# 15_BOOT.net
KiCad netlist of a schematic drawn in Altium Designer
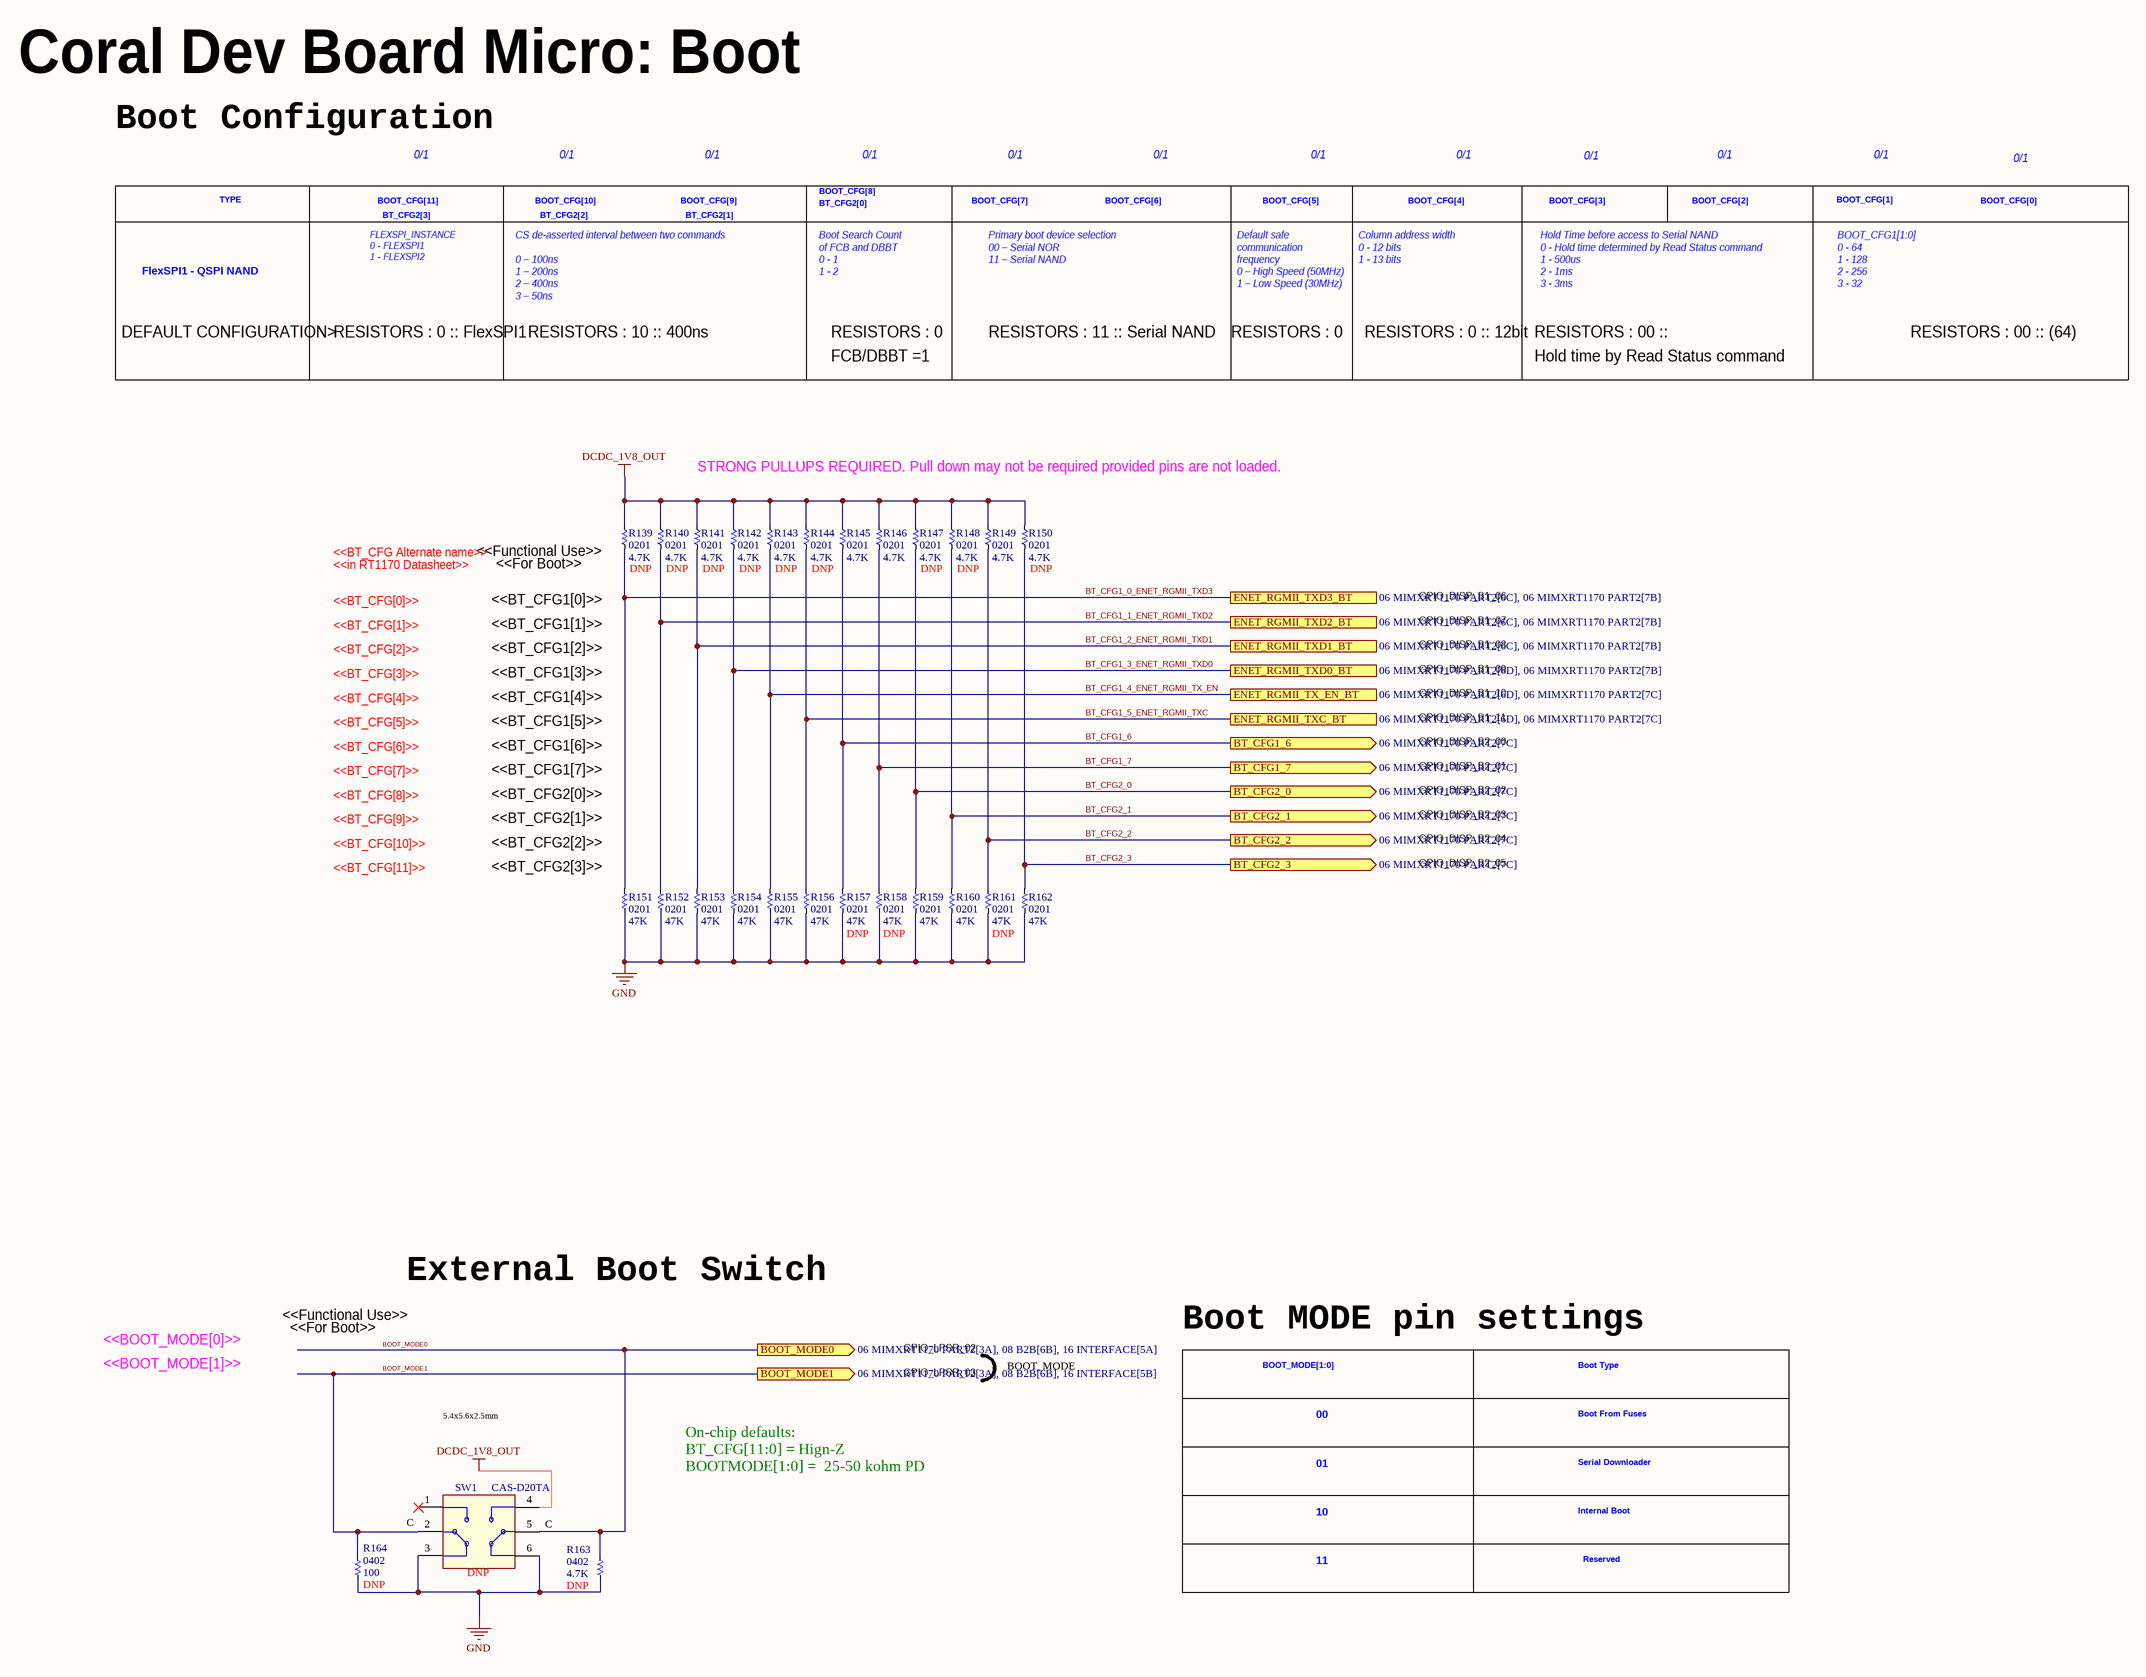
[diagram p0: 15 BOOT.SchDoc]

(export (version "E")
  (design (tool "Eeschema 10.0.6"))
  (components
    (comp (ref "R139")
      (value "4.7K")
      (footprint "R0201")
      (description "RES, 4.7K, 5%, 1/20W, 0201")
      (fields
        (field (name "MFG") "YAGEO")
        (field (name "PACKAGE") "0201")
        (field (name "POWER") "1/20W")
        (field (name "DNP") "DNP")
      )
      (libsource (lib "AltiumReleaseLibDB") (part "__Template_Resistor"))
    )
    (comp (ref "R140")
      (value "4.7K")
      (footprint "R0201")
      (description "RES, 4.7K, 5%, 1/20W, 0201")
      (fields
        (field (name "MFG") "YAGEO")
        (field (name "PACKAGE") "0201")
        (field (name "POWER") "1/20W")
        (field (name "DNP") "DNP")
      )
      (libsource (lib "AltiumReleaseLibDB") (part "__Template_Resistor"))
    )
    (comp (ref "R141")
      (value "4.7K")
      (footprint "R0201")
      (description "RES, 4.7K, 5%, 1/20W, 0201")
      (fields
        (field (name "MFG") "YAGEO")
        (field (name "PACKAGE") "0201")
        (field (name "POWER") "1/20W")
        (field (name "DNP") "DNP")
      )
      (libsource (lib "AltiumReleaseLibDB") (part "__Template_Resistor"))
    )
    (comp (ref "R142")
      (value "4.7K")
      (footprint "R0201")
      (description "RES, 4.7K, 5%, 1/20W, 0201")
      (fields
        (field (name "MFG") "YAGEO")
        (field (name "PACKAGE") "0201")
        (field (name "POWER") "1/20W")
        (field (name "DNP") "DNP")
      )
      (libsource (lib "AltiumReleaseLibDB") (part "__Template_Resistor"))
    )
    (comp (ref "R143")
      (value "4.7K")
      (footprint "R0201")
      (description "RES, 4.7K, 5%, 1/20W, 0201")
      (fields
        (field (name "MFG") "YAGEO")
        (field (name "PACKAGE") "0201")
        (field (name "POWER") "1/20W")
        (field (name "DNP") "DNP")
      )
      (libsource (lib "AltiumReleaseLibDB") (part "__Template_Resistor"))
    )
    (comp (ref "R144")
      (value "4.7K")
      (footprint "R0201")
      (description "RES, 4.7K, 5%, 1/20W, 0201")
      (fields
        (field (name "MFG") "YAGEO")
        (field (name "PACKAGE") "0201")
        (field (name "POWER") "1/20W")
        (field (name "DNP") "DNP")
      )
      (libsource (lib "AltiumReleaseLibDB") (part "__Template_Resistor"))
    )
    (comp (ref "R145")
      (value "4.7K")
      (footprint "R0201")
      (description "RES, 4.7K, 5%, 1/20W, 0201")
      (fields (field (name "MFG") "YAGEO") (field (name "PACKAGE") "0201") (field (name "POWER") "1/20W"))
      (libsource (lib "AltiumReleaseLibDB") (part "__Template_Resistor"))
    )
    (comp (ref "R146")
      (value "4.7K")
      (footprint "R0201")
      (description "RES, 4.7K, 5%, 1/20W, 0201")
      (fields (field (name "MFG") "YAGEO") (field (name "PACKAGE") "0201") (field (name "POWER") "1/20W"))
      (libsource (lib "AltiumReleaseLibDB") (part "__Template_Resistor"))
    )
    (comp (ref "R147")
      (value "4.7K")
      (footprint "R0201")
      (description "RES, 4.7K, 5%, 1/20W, 0201")
      (fields
        (field (name "MFG") "YAGEO")
        (field (name "PACKAGE") "0201")
        (field (name "POWER") "1/20W")
        (field (name "DNP") "DNP")
      )
      (libsource (lib "AltiumReleaseLibDB") (part "__Template_Resistor"))
    )
    (comp (ref "R148")
      (value "4.7K")
      (footprint "R0201")
      (description "RES, 4.7K, 5%, 1/20W, 0201")
      (fields
        (field (name "MFG") "YAGEO")
        (field (name "PACKAGE") "0201")
        (field (name "POWER") "1/20W")
        (field (name "DNP") "DNP")
      )
      (libsource (lib "AltiumReleaseLibDB") (part "__Template_Resistor"))
    )
    (comp (ref "R149")
      (value "4.7K")
      (footprint "R0201")
      (description "RES, 4.7K, 5%, 1/20W, 0201")
      (fields (field (name "MFG") "YAGEO") (field (name "PACKAGE") "0201") (field (name "POWER") "1/20W"))
      (libsource (lib "AltiumReleaseLibDB") (part "__Template_Resistor"))
    )
    (comp (ref "R150")
      (value "4.7K")
      (footprint "R0201")
      (description "RES, 4.7K, 5%, 1/20W, 0201")
      (fields
        (field (name "MFG") "YAGEO")
        (field (name "PACKAGE") "0201")
        (field (name "POWER") "1/20W")
        (field (name "DNP") "DNP")
      )
      (libsource (lib "AltiumReleaseLibDB") (part "__Template_Resistor"))
    )
    (comp (ref "R151")
      (value "47K")
      (footprint "R0201")
      (description "RES, 47K, 5%, 1/20W, 0201")
      (fields (field (name "MFG") "PANASONIC") (field (name "PACKAGE") "0201") (field (name "POWER") "1/20W"))
      (libsource (lib "AltiumReleaseLibDB") (part "__Template_Resistor"))
    )
    (comp (ref "R152")
      (value "47K")
      (footprint "R0201")
      (description "RES, 47K, 5%, 1/20W, 0201")
      (fields (field (name "MFG") "PANASONIC") (field (name "PACKAGE") "0201") (field (name "POWER") "1/20W"))
      (libsource (lib "AltiumReleaseLibDB") (part "__Template_Resistor"))
    )
    (comp (ref "R153")
      (value "47K")
      (footprint "R0201")
      (description "RES, 47K, 5%, 1/20W, 0201")
      (fields (field (name "MFG") "PANASONIC") (field (name "PACKAGE") "0201") (field (name "POWER") "1/20W"))
      (libsource (lib "AltiumReleaseLibDB") (part "__Template_Resistor"))
    )
    (comp (ref "R154")
      (value "47K")
      (footprint "R0201")
      (description "RES, 47K, 5%, 1/20W, 0201")
      (fields (field (name "MFG") "PANASONIC") (field (name "PACKAGE") "0201") (field (name "POWER") "1/20W"))
      (libsource (lib "AltiumReleaseLibDB") (part "__Template_Resistor"))
    )
    (comp (ref "R155")
      (value "47K")
      (footprint "R0201")
      (description "RES, 47K, 5%, 1/20W, 0201")
      (fields (field (name "MFG") "PANASONIC") (field (name "PACKAGE") "0201") (field (name "POWER") "1/20W"))
      (libsource (lib "AltiumReleaseLibDB") (part "__Template_Resistor"))
    )
    (comp (ref "R156")
      (value "47K")
      (footprint "R0201")
      (description "RES, 47K, 5%, 1/20W, 0201")
      (fields (field (name "MFG") "PANASONIC") (field (name "PACKAGE") "0201") (field (name "POWER") "1/20W"))
      (libsource (lib "AltiumReleaseLibDB") (part "__Template_Resistor"))
    )
    (comp (ref "R157")
      (value "47K")
      (footprint "R0201")
      (description "RES, 47K, 5%, 1/20W, 0201")
      (fields
        (field (name "MFG") "PANASONIC")
        (field (name "PACKAGE") "0201")
        (field (name "POWER") "1/20W")
        (field (name "DNP") "DNP")
      )
      (libsource (lib "AltiumReleaseLibDB") (part "__Template_Resistor"))
    )
    (comp (ref "R158")
      (value "47K")
      (footprint "R0201")
      (description "RES, 47K, 5%, 1/20W, 0201")
      (fields
        (field (name "MFG") "PANASONIC")
        (field (name "PACKAGE") "0201")
        (field (name "POWER") "1/20W")
        (field (name "DNP") "DNP")
      )
      (libsource (lib "AltiumReleaseLibDB") (part "__Template_Resistor"))
    )
    (comp (ref "R159")
      (value "47K")
      (footprint "R0201")
      (description "RES, 47K, 5%, 1/20W, 0201")
      (fields (field (name "MFG") "PANASONIC") (field (name "PACKAGE") "0201") (field (name "POWER") "1/20W"))
      (libsource (lib "AltiumReleaseLibDB") (part "__Template_Resistor"))
    )
    (comp (ref "R160")
      (value "47K")
      (footprint "R0201")
      (description "RES, 47K, 5%, 1/20W, 0201")
      (fields (field (name "MFG") "PANASONIC") (field (name "PACKAGE") "0201") (field (name "POWER") "1/20W"))
      (libsource (lib "AltiumReleaseLibDB") (part "__Template_Resistor"))
    )
    (comp (ref "R161")
      (value "47K")
      (footprint "R0201")
      (description "RES, 47K, 5%, 1/20W, 0201")
      (fields
        (field (name "MFG") "PANASONIC")
        (field (name "PACKAGE") "0201")
        (field (name "POWER") "1/20W")
        (field (name "DNP") "DNP")
      )
      (libsource (lib "AltiumReleaseLibDB") (part "__Template_Resistor"))
    )
    (comp (ref "R162")
      (value "47K")
      (footprint "R0201")
      (description "RES, 47K, 5%, 1/20W, 0201")
      (fields (field (name "MFG") "PANASONIC") (field (name "PACKAGE") "0201") (field (name "POWER") "1/20W"))
      (libsource (lib "AltiumReleaseLibDB") (part "__Template_Resistor"))
    )
    (comp (ref "R163")
      (value "4.7K")
      (footprint "R0402")
      (description "RES, 4.7K, 1%, 1/10W, 0402")
      (fields
        (field (name "MFG") "PANASONIC")
        (field (name "PACKAGE") "0402")
        (field (name "POWER") "1/10W")
        (field (name "DNP") "DNP")
      )
      (libsource (lib "AltiumReleaseLibDB") (part "__Template_Resistor"))
    )
    (comp (ref "R164")
      (value "100")
      (footprint "R0402")
      (description "RES, 100, 5%, 1/16W, 0402, AUTO GRADE")
      (fields
        (field (name "MFG") "VISHAY")
        (field (name "PACKAGE") "0402")
        (field (name "POWER") "1/16W")
        (field (name "DNP") "DNP")
      )
      (libsource (lib "AltiumReleaseLibDB") (part "__Template_Resistor"))
    )
    (comp (ref "SW1")
      (value "SWITCH_NIDEC_CAS-D20TA")
      (footprint "SWITCH_CAS-D20TA")
      (description "SW, SLIDE, SPDTx2, 100mA, 6VDC, 2-POS, ON-ON, GOLD, SMT")
      (fields
        (field (name "MFG") "Nidec Copal Electronics")
        (field (name "MFG P/N") "CAS-D20TA")
        (field (name "DNP") "DNP")
      )
      (libsource (lib "AltiumReleaseLibDB") (part "SWITCH_NIDEC_CAS-D20TA"))
    )
  )
  (nets
    (net (code "1") (name "/BOOT_MODE0") (class "Default")
      (node (ref "R163") (pin "2") (pintype "passive"))
      (node (ref "SW1") (pin "5") (pinfunction "5_5") (pintype "passive"))
    )
    (net (code "2") (name "/BOOT_MODE1") (class "Default")
      (node (ref "R164") (pin "2") (pintype "passive"))
      (node (ref "SW1") (pin "2") (pinfunction "2_2") (pintype "passive"))
    )
    (net (code "3") (name "/BT_CFG1_0_ENET_RGMII_TXD3") (class "Default")
      (node (ref "R139") (pin "1") (pintype "passive"))
      (node (ref "R151") (pin "1") (pintype "passive"))
    )
    (net (code "4") (name "/BT_CFG1_1_ENET_RGMII_TXD2") (class "Default")
      (node (ref "R140") (pin "1") (pintype "passive"))
      (node (ref "R152") (pin "1") (pintype "passive"))
    )
    (net (code "5") (name "/BT_CFG1_2_ENET_RGMII_TXD1") (class "Default")
      (node (ref "R141") (pin "1") (pintype "passive"))
      (node (ref "R153") (pin "1") (pintype "passive"))
    )
    (net (code "6") (name "/BT_CFG1_3_ENET_RGMII_TXD0") (class "Default")
      (node (ref "R142") (pin "1") (pintype "passive"))
      (node (ref "R154") (pin "1") (pintype "passive"))
    )
    (net (code "7") (name "/BT_CFG1_4_ENET_RGMII_TX_EN") (class "Default")
      (node (ref "R143") (pin "1") (pintype "passive"))
      (node (ref "R155") (pin "1") (pintype "passive"))
    )
    (net (code "8") (name "/BT_CFG1_5_ENET_RGMII_TXC") (class "Default")
      (node (ref "R144") (pin "1") (pintype "passive"))
      (node (ref "R156") (pin "1") (pintype "passive"))
    )
    (net (code "9") (name "/BT_CFG1_6") (class "Default")
      (node (ref "R145") (pin "1") (pintype "passive"))
      (node (ref "R157") (pin "1") (pintype "passive"))
    )
    (net (code "10") (name "/BT_CFG1_7") (class "Default")
      (node (ref "R146") (pin "1") (pintype "passive"))
      (node (ref "R158") (pin "1") (pintype "passive"))
    )
    (net (code "11") (name "/BT_CFG2_0") (class "Default")
      (node (ref "R147") (pin "1") (pintype "passive"))
      (node (ref "R159") (pin "1") (pintype "passive"))
    )
    (net (code "12") (name "/BT_CFG2_1") (class "Default")
      (node (ref "R148") (pin "1") (pintype "passive"))
      (node (ref "R160") (pin "1") (pintype "passive"))
    )
    (net (code "13") (name "/BT_CFG2_2") (class "Default")
      (node (ref "R149") (pin "1") (pintype "passive"))
      (node (ref "R161") (pin "1") (pintype "passive"))
    )
    (net (code "14") (name "/BT_CFG2_3") (class "Default")
      (node (ref "R150") (pin "1") (pintype "passive"))
      (node (ref "R162") (pin "1") (pintype "passive"))
    )
    (net (code "15") (name "DCDC_1V8_OUT") (class "Default")
      (node (ref "R139") (pin "2") (pintype "passive"))
      (node (ref "R140") (pin "2") (pintype "passive"))
      (node (ref "R141") (pin "2") (pintype "passive"))
      (node (ref "R142") (pin "2") (pintype "passive"))
      (node (ref "R143") (pin "2") (pintype "passive"))
      (node (ref "R144") (pin "2") (pintype "passive"))
      (node (ref "R145") (pin "2") (pintype "passive"))
      (node (ref "R146") (pin "2") (pintype "passive"))
      (node (ref "R147") (pin "2") (pintype "passive"))
      (node (ref "R148") (pin "2") (pintype "passive"))
      (node (ref "R149") (pin "2") (pintype "passive"))
      (node (ref "R150") (pin "2") (pintype "passive"))
      (node (ref "SW1") (pin "4") (pinfunction "4_4") (pintype "passive"))
    )
    (net (code "16") (name "GND") (class "Default")
      (node (ref "R151") (pin "2") (pintype "passive"))
      (node (ref "R152") (pin "2") (pintype "passive"))
      (node (ref "R153") (pin "2") (pintype "passive"))
      (node (ref "R154") (pin "2") (pintype "passive"))
      (node (ref "R155") (pin "2") (pintype "passive"))
      (node (ref "R156") (pin "2") (pintype "passive"))
      (node (ref "R157") (pin "2") (pintype "passive"))
      (node (ref "R158") (pin "2") (pintype "passive"))
      (node (ref "R159") (pin "2") (pintype "passive"))
      (node (ref "R160") (pin "2") (pintype "passive"))
      (node (ref "R161") (pin "2") (pintype "passive"))
      (node (ref "R162") (pin "2") (pintype "passive"))
      (node (ref "R163") (pin "1") (pintype "passive"))
      (node (ref "R164") (pin "1") (pintype "passive"))
      (node (ref "SW1") (pin "3") (pinfunction "3_3") (pintype "passive"))
      (node (ref "SW1") (pin "6") (pinfunction "6_6") (pintype "passive"))
    )
    (net (code "17") (name "unconnected-(SW1-Pad1)") (class "Default")
      (node (ref "SW1") (pin "1") (pinfunction "1_1") (pintype "passive+no_connect"))
    )
  )
)
